# board-Type-C-31-M-17.net
KiCad netlist of a schematic drawn in EAGLE
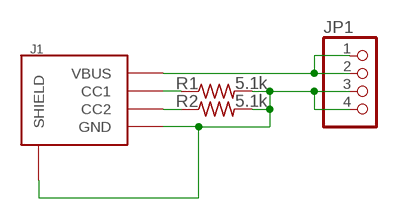
[diagram p0: schematic, sheet 1]

(export (version "E")
  (design (tool "Eeschema 10.0.6"))
  (components
    (comp (ref "J1")
      (value "USB-TYPE-C-31-M-17")
      (footprint "eagle-import:USB-TYPE-C-31-M-17")
      (libsource (lib "eagle-import") (part "USB-TYPE-C-31-M-17"))
    )
    (comp (ref "JP1")
      (value "PINHD-1X4")
      (footprint "eagle-import:1X04")
      (libsource (lib "eagle-import") (part "PINHD-1X4"))
    )
    (comp (ref "R1")
      (value "5.1k")
      (footprint "eagle-import:R0603")
      (libsource (lib "eagle-import") (part "RR0603"))
    )
    (comp (ref "R2")
      (value "5.1k")
      (footprint "eagle-import:R0603")
      (libsource (lib "eagle-import") (part "RR0603"))
    )
  )
  (nets
    (net (code "1") (name "Net-(J1-GND-PadGND_2)") (class "Default")
      (node (ref "J1") (pin "GND") (pinfunction "GND_GND") (pintype "bidirectional"))
      (node (ref "J1") (pin "GND_2") (pinfunction "GND_GND_2") (pintype "bidirectional"))
      (node (ref "J1") (pin "SHLD-B1") (pinfunction "SHIELD_SHLD-B1") (pintype "bidirectional"))
      (node (ref "J1") (pin "SHLD-B2") (pinfunction "SHIELD_SHLD-B2") (pintype "bidirectional"))
      (node (ref "J1") (pin "SHLD-B3") (pinfunction "SHIELD_SHLD-B3") (pintype "bidirectional"))
      (node (ref "J1") (pin "SHLD-B4") (pinfunction "SHIELD_SHLD-B4") (pintype "bidirectional"))
      (node (ref "J1") (pin "SHLD-T1") (pinfunction "SHIELD_SHLD-T1") (pintype "bidirectional"))
      (node (ref "J1") (pin "SHLD-T2") (pinfunction "SHIELD_SHLD-T2") (pintype "bidirectional"))
      (node (ref "J1") (pin "SHLD-T3") (pinfunction "SHIELD_SHLD-T3") (pintype "bidirectional"))
      (node (ref "J1") (pin "SHLD-T4") (pinfunction "SHIELD_SHLD-T4") (pintype "bidirectional"))
      (node (ref "JP1") (pin "3") (pinfunction "3_3") (pintype "passive"))
      (node (ref "JP1") (pin "4") (pinfunction "4_4") (pintype "passive"))
      (node (ref "R1") (pin "2") (pinfunction "2_2") (pintype "passive"))
      (node (ref "R2") (pin "2") (pinfunction "2_2") (pintype "passive"))
    )
    (net (code "2") (name "Net-(J1-PadCC1)") (class "Default")
      (node (ref "J1") (pin "CC1") (pinfunction "CC1_CC1") (pintype "bidirectional"))
      (node (ref "R1") (pin "1") (pinfunction "1_1") (pintype "passive"))
    )
    (net (code "3") (name "Net-(J1-PadCC2)") (class "Default")
      (node (ref "J1") (pin "CC2") (pinfunction "CC2_CC2") (pintype "bidirectional"))
      (node (ref "R2") (pin "1") (pinfunction "1_1") (pintype "passive"))
    )
    (net (code "4") (name "Net-(J1-PadVBUS)") (class "Default")
      (node (ref "J1") (pin "VBUS") (pinfunction "VBUS_VBUS") (pintype "bidirectional"))
      (node (ref "J1") (pin "VBUS_2") (pinfunction "VBUS_VBUS_2") (pintype "bidirectional"))
      (node (ref "JP1") (pin "1") (pinfunction "1_1") (pintype "passive"))
      (node (ref "JP1") (pin "2") (pinfunction "2_2") (pintype "passive"))
    )
  )
)
